# IO.net
KiCad netlist of a schematic drawn in Altium Designer
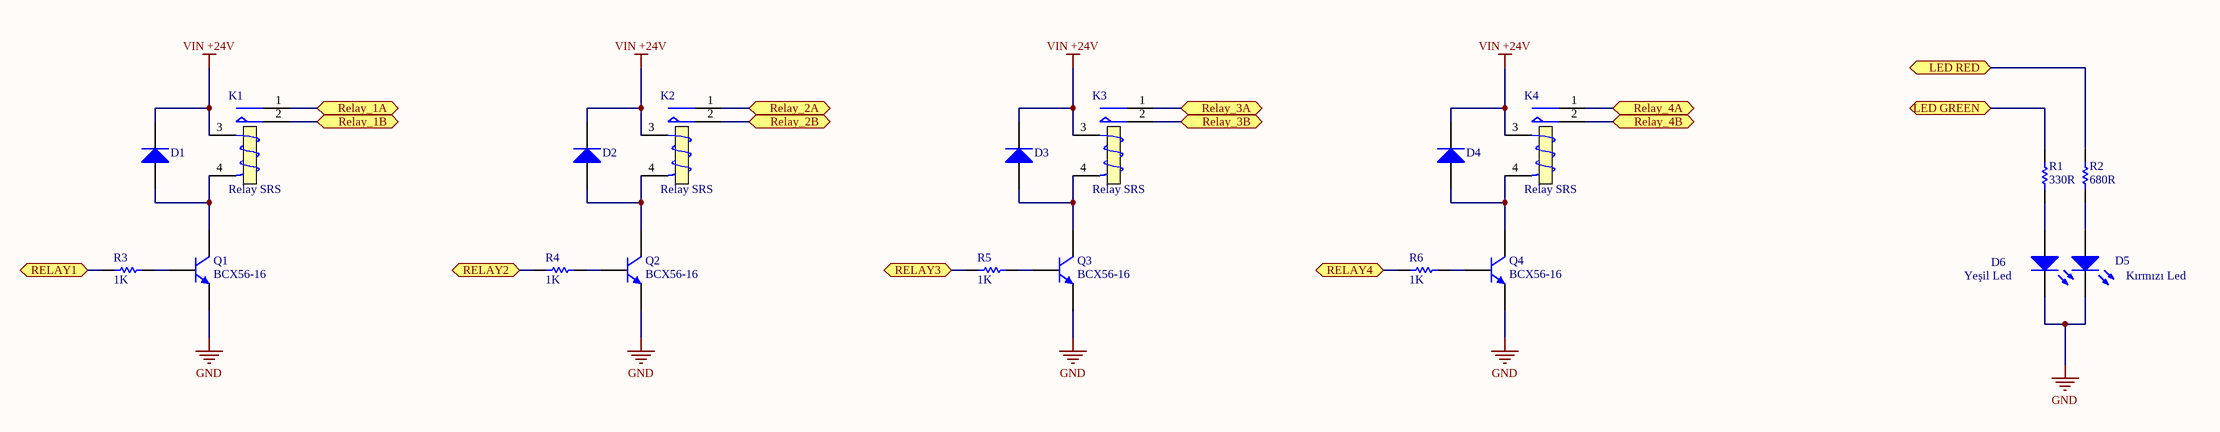
[diagram p0: IO.SchDoc]

(export (version "E")
  (design (tool "Eeschema 10.0.6"))
  (components
    (comp (ref "D1")
      (value "Diode 1N4007")
      (footprint "DO214")
      (description "1 Amp General Purpose Rectifier")
      (fields (field (name "PUBLISHER") "Altium Limited"))
      (libsource (lib "Erdem_05112012") (part "Diode 1N4007"))
    )
    (comp (ref "D2")
      (value "Diode 1N4007")
      (footprint "DO214")
      (description "1 Amp General Purpose Rectifier")
      (fields (field (name "PUBLISHER") "Altium Limited"))
      (libsource (lib "Erdem_05112012") (part "Diode 1N4007"))
    )
    (comp (ref "D3")
      (value "Diode 1N4007")
      (footprint "DO214")
      (description "1 Amp General Purpose Rectifier")
      (fields (field (name "PUBLISHER") "Altium Limited"))
      (libsource (lib "Erdem_05112012") (part "Diode 1N4007"))
    )
    (comp (ref "D4")
      (value "Diode 1N4007")
      (footprint "DO214")
      (description "1 Amp General Purpose Rectifier")
      (fields (field (name "PUBLISHER") "Altium Limited"))
      (libsource (lib "Erdem_05112012") (part "Diode 1N4007"))
    )
    (comp (ref "D5")
      (value "Yeşil Led")
      (footprint "6-0805 - LED")
      (description "Typical INFRARED GaAs LED")
      (fields (field (name "PUBLISHER") "Altium Limited"))
      (libsource (lib "Erdem_05112012") (part "LED"))
    )
    (comp (ref "D6")
      (value "Kırmızı Led")
      (footprint "6-0805 - LED")
      (description "Typical INFRARED GaAs LED")
      (fields (field (name "PUBLISHER") "Altium Limited"))
      (libsource (lib "Erdem_05112012") (part "LED"))
    )
    (comp (ref "K1")
      (value "Relay SRS")
      (footprint "RELAY ALQ324")
      (description "Relay ALQ324")
      (fields (field (name "PUBLISHER") "Altium Limited"))
      (libsource (lib "Erdem_05112012") (part "Relay ALQ324"))
    )
    (comp (ref "K2")
      (value "Relay SRS")
      (footprint "RELAY ALQ324")
      (description "Relay ALQ324")
      (fields (field (name "PUBLISHER") "Altium Limited"))
      (libsource (lib "Erdem_05112012") (part "Relay ALQ324"))
    )
    (comp (ref "K3")
      (value "Relay SRS")
      (footprint "RELAY ALQ324")
      (description "Relay ALQ324")
      (fields (field (name "PUBLISHER") "Altium Limited"))
      (libsource (lib "Erdem_05112012") (part "Relay ALQ324"))
    )
    (comp (ref "K4")
      (value "Relay SRS")
      (footprint "RELAY ALQ324")
      (description "Relay ALQ324")
      (fields (field (name "PUBLISHER") "Altium Limited"))
      (libsource (lib "Erdem_05112012") (part "Relay ALQ324"))
    )
    (comp (ref "Q1")
      (value "BCX56-16")
      (footprint "SOT89M")
      (description "NPN General-purpose Transistor")
      (fields (field (name "PUBLISHER") "Altium Limited"))
      (libsource (lib "Erdem_05112012") (part "BCX56-16"))
    )
    (comp (ref "Q2")
      (value "BCX56-16")
      (footprint "SOT89M")
      (description "NPN General-purpose Transistor")
      (fields (field (name "PUBLISHER") "Altium Limited"))
      (libsource (lib "Erdem_05112012") (part "BCX56-16"))
    )
    (comp (ref "Q3")
      (value "BCX56-16")
      (footprint "SOT89M")
      (description "NPN General-purpose Transistor")
      (fields (field (name "PUBLISHER") "Altium Limited"))
      (libsource (lib "Erdem_05112012") (part "BCX56-16"))
    )
    (comp (ref "Q4")
      (value "BCX56-16")
      (footprint "SOT89M")
      (description "NPN General-purpose Transistor")
      (fields (field (name "PUBLISHER") "Altium Limited"))
      (libsource (lib "Erdem_05112012") (part "BCX56-16"))
    )
    (comp (ref "R1")
      (value "330R")
      (footprint "6-0805 - big")
      (description "Resistor")
      (fields (field (name "Comment") "Res1") (field (name "PUBLISHER") "Altium Limited"))
      (libsource (lib "Erdem_05112012") (part "Res1"))
    )
    (comp (ref "R2")
      (value "680R")
      (footprint "6-0805 - big")
      (description "Resistor")
      (fields (field (name "Comment") "Res1") (field (name "PUBLISHER") "Altium Limited"))
      (libsource (lib "Erdem_05112012") (part "Res1"))
    )
    (comp (ref "R3")
      (value "1K")
      (footprint "6-0805")
      (description "Resistor")
      (fields (field (name "Comment") "Res1") (field (name "PUBLISHER") "Altium Limited"))
      (libsource (lib "Erdem_05112012") (part "Res1"))
    )
    (comp (ref "R4")
      (value "1K")
      (footprint "6-0805")
      (description "Resistor")
      (fields (field (name "Comment") "Res1") (field (name "PUBLISHER") "Altium Limited"))
      (libsource (lib "Erdem_05112012") (part "Res1"))
    )
    (comp (ref "R5")
      (value "1K")
      (footprint "6-0805")
      (description "Resistor")
      (fields (field (name "Comment") "Res1") (field (name "PUBLISHER") "Altium Limited"))
      (libsource (lib "Erdem_05112012") (part "Res1"))
    )
    (comp (ref "R6")
      (value "1K")
      (footprint "6-0805")
      (description "Resistor")
      (fields (field (name "Comment") "Res1") (field (name "PUBLISHER") "Altium Limited"))
      (libsource (lib "Erdem_05112012") (part "Res1"))
    )
  )
  (nets
    (net (code "1") (name "/LED GREEN") (class "Default")
      (node (ref "R1") (pin "2") (pinfunction "2_2") (pintype "passive"))
    )
    (net (code "2") (name "/LED RED") (class "Default")
      (node (ref "R2") (pin "2") (pinfunction "2_2") (pintype "passive"))
    )
    (net (code "3") (name "/RELAY1") (class "Default")
      (node (ref "R3") (pin "1") (pinfunction "1_1") (pintype "passive"))
    )
    (net (code "4") (name "/RELAY2") (class "Default")
      (node (ref "R4") (pin "1") (pinfunction "1_1") (pintype "passive"))
    )
    (net (code "5") (name "/RELAY3") (class "Default")
      (node (ref "R5") (pin "1") (pinfunction "1_1") (pintype "passive"))
    )
    (net (code "6") (name "/RELAY4") (class "Default")
      (node (ref "R6") (pin "1") (pinfunction "1_1") (pintype "passive"))
    )
    (net (code "7") (name "/Relay_1A") (class "Default")
      (node (ref "K1") (pin "1") (pinfunction "COM_1") (pintype "passive"))
    )
    (net (code "8") (name "/Relay_1B") (class "Default")
      (node (ref "K1") (pin "2") (pinfunction "NC_2") (pintype "passive"))
    )
    (net (code "9") (name "/Relay_2A") (class "Default")
      (node (ref "K2") (pin "1") (pinfunction "COM_1") (pintype "passive"))
    )
    (net (code "10") (name "/Relay_2B") (class "Default")
      (node (ref "K2") (pin "2") (pinfunction "NC_2") (pintype "passive"))
    )
    (net (code "11") (name "/Relay_3A") (class "Default")
      (node (ref "K3") (pin "1") (pinfunction "COM_1") (pintype "passive"))
    )
    (net (code "12") (name "/Relay_3B") (class "Default")
      (node (ref "K3") (pin "2") (pinfunction "NC_2") (pintype "passive"))
    )
    (net (code "13") (name "/Relay_4A") (class "Default")
      (node (ref "K4") (pin "1") (pinfunction "COM_1") (pintype "passive"))
    )
    (net (code "14") (name "/Relay_4B") (class "Default")
      (node (ref "K4") (pin "2") (pinfunction "NC_2") (pintype "passive"))
    )
    (net (code "15") (name "GND") (class "Default")
      (node (ref "D5") (pin "2") (pinfunction "K_2") (pintype "passive"))
      (node (ref "D6") (pin "2") (pinfunction "K_2") (pintype "passive"))
      (node (ref "Q1") (pin "3") (pinfunction "E_3") (pintype "passive"))
      (node (ref "Q2") (pin "3") (pinfunction "E_3") (pintype "passive"))
      (node (ref "Q3") (pin "3") (pinfunction "E_3") (pintype "passive"))
      (node (ref "Q4") (pin "3") (pinfunction "E_3") (pintype "passive"))
    )
    (net (code "16") (name "Net-(D1-A)") (class "Default")
      (node (ref "D1") (pin "1") (pinfunction "A_1") (pintype "passive"))
      (node (ref "K1") (pin "4") (pinfunction "T2_4") (pintype "passive"))
      (node (ref "Q1") (pin "2") (pinfunction "C_2") (pintype "passive"))
    )
    (net (code "17") (name "Net-(D2-A)") (class "Default")
      (node (ref "D2") (pin "1") (pinfunction "A_1") (pintype "passive"))
      (node (ref "K2") (pin "4") (pinfunction "T2_4") (pintype "passive"))
      (node (ref "Q2") (pin "2") (pinfunction "C_2") (pintype "passive"))
    )
    (net (code "18") (name "Net-(D3-A)") (class "Default")
      (node (ref "D3") (pin "1") (pinfunction "A_1") (pintype "passive"))
      (node (ref "K3") (pin "4") (pinfunction "T2_4") (pintype "passive"))
      (node (ref "Q3") (pin "2") (pinfunction "C_2") (pintype "passive"))
    )
    (net (code "19") (name "Net-(D4-A)") (class "Default")
      (node (ref "D4") (pin "1") (pinfunction "A_1") (pintype "passive"))
      (node (ref "K4") (pin "4") (pinfunction "T2_4") (pintype "passive"))
      (node (ref "Q4") (pin "2") (pinfunction "C_2") (pintype "passive"))
    )
    (net (code "20") (name "Net-(D5-A)") (class "Default")
      (node (ref "D5") (pin "1") (pinfunction "A_1") (pintype "passive"))
      (node (ref "R2") (pin "1") (pinfunction "1_1") (pintype "passive"))
    )
    (net (code "21") (name "Net-(D6-A)") (class "Default")
      (node (ref "D6") (pin "1") (pinfunction "A_1") (pintype "passive"))
      (node (ref "R1") (pin "1") (pinfunction "1_1") (pintype "passive"))
    )
    (net (code "22") (name "Net-(Q1-B)") (class "Default")
      (node (ref "Q1") (pin "1") (pinfunction "B_1") (pintype "passive"))
      (node (ref "R3") (pin "2") (pinfunction "2_2") (pintype "passive"))
    )
    (net (code "23") (name "Net-(Q2-B)") (class "Default")
      (node (ref "Q2") (pin "1") (pinfunction "B_1") (pintype "passive"))
      (node (ref "R4") (pin "2") (pinfunction "2_2") (pintype "passive"))
    )
    (net (code "24") (name "Net-(Q3-B)") (class "Default")
      (node (ref "Q3") (pin "1") (pinfunction "B_1") (pintype "passive"))
      (node (ref "R5") (pin "2") (pinfunction "2_2") (pintype "passive"))
    )
    (net (code "25") (name "Net-(Q4-B)") (class "Default")
      (node (ref "Q4") (pin "1") (pinfunction "B_1") (pintype "passive"))
      (node (ref "R6") (pin "2") (pinfunction "2_2") (pintype "passive"))
    )
    (net (code "26") (name "VIN +24V") (class "Default")
      (node (ref "D1") (pin "2") (pinfunction "K_2") (pintype "passive"))
      (node (ref "D2") (pin "2") (pinfunction "K_2") (pintype "passive"))
      (node (ref "D3") (pin "2") (pinfunction "K_2") (pintype "passive"))
      (node (ref "D4") (pin "2") (pinfunction "K_2") (pintype "passive"))
      (node (ref "K1") (pin "3") (pinfunction "T1_3") (pintype "passive"))
      (node (ref "K2") (pin "3") (pinfunction "T1_3") (pintype "passive"))
      (node (ref "K3") (pin "3") (pinfunction "T1_3") (pintype "passive"))
      (node (ref "K4") (pin "3") (pinfunction "T1_3") (pintype "passive"))
    )
  )
)
